# LineAmp.net
KiCad netlist of a schematic drawn in EAGLE
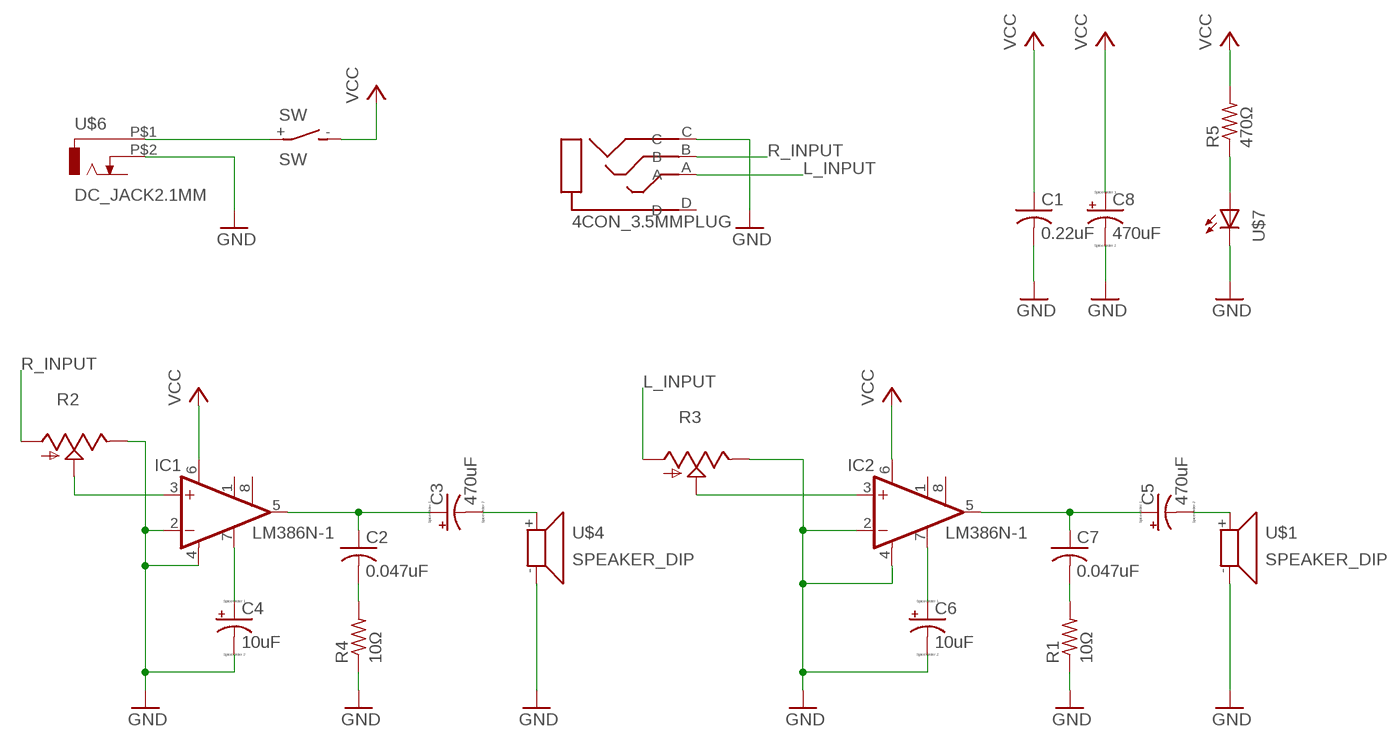
[diagram p0: schematic, sheet 1]

(export (version "E")
  (design (tool "Eeschema 10.0.6"))
  (components
    (comp (ref "C1")
      (value "0.22uF")
      (footprint "eagle-import:C075-042X103")
      (libsource (lib "eagle-import") (part "C-US075-042X103"))
    )
    (comp (ref "C2")
      (value "0.047uF")
      (footprint "eagle-import:C050-024X044")
      (libsource (lib "eagle-import") (part "C-US050-024X044"))
    )
    (comp (ref "C3")
      (value "470uF")
      (footprint "eagle-import:E7,5-16")
      (libsource (lib "eagle-import") (part "CPOL-USE7.5-16"))
    )
    (comp (ref "C4")
      (value "10uF")
      (footprint "eagle-import:E2-5")
      (libsource (lib "eagle-import") (part "CPOL-USE2-5"))
    )
    (comp (ref "C5")
      (value "470uF")
      (footprint "eagle-import:E7,5-16")
      (libsource (lib "eagle-import") (part "CPOL-USE7.5-16"))
    )
    (comp (ref "C6")
      (value "10uF")
      (footprint "eagle-import:E2-5")
      (libsource (lib "eagle-import") (part "CPOL-USE2-5"))
    )
    (comp (ref "C7")
      (value "0.047uF")
      (footprint "eagle-import:C050-024X044")
      (libsource (lib "eagle-import") (part "C-US050-024X044"))
    )
    (comp (ref "C8")
      (value "470uF")
      (footprint "eagle-import:E7,5-16")
      (libsource (lib "eagle-import") (part "CPOL-USE7.5-16"))
    )
    (comp (ref "IC1")
      (value "LM386N-1")
      (footprint "eagle-import:DIL08")
      (libsource (lib "eagle-import") (part "LM386?-N1"))
    )
    (comp (ref "IC2")
      (value "LM386N-1")
      (footprint "eagle-import:DIL08")
      (libsource (lib "eagle-import") (part "LM386?-N1"))
    )
    (comp (ref "R1")
      (value "10Ω")
      (footprint "eagle-import:M1206")
      (libsource (lib "eagle-import") (part "R-US_M1206"))
    )
    (comp (ref "R2")
      (value "TRIM_US-ALPS-PANEL")
      (footprint "eagle-import:ALPS-POT-PANEL")
      (libsource (lib "eagle-import") (part "TRIM_US-ALPS-PANEL"))
    )
    (comp (ref "R3")
      (value "TRIM_US-ALPS-PANEL")
      (footprint "eagle-import:ALPS-POT-PANEL")
      (libsource (lib "eagle-import") (part "TRIM_US-ALPS-PANEL"))
    )
    (comp (ref "R4")
      (value "10Ω")
      (footprint "eagle-import:M1206")
      (libsource (lib "eagle-import") (part "R-US_M1206"))
    )
    (comp (ref "R5")
      (value "470Ω")
      (footprint "eagle-import:M1206")
      (libsource (lib "eagle-import") (part "R-US_M1206"))
    )
    (comp (ref "SW")
      (value "SW")
      (footprint "eagle-import:2PIN_DIP")
      (libsource (lib "eagle-import") (part "SW"))
    )
    (comp (ref "U$1")
      (value "SPEAKER_DIP")
      (footprint "eagle-import:2PIN_DIP")
      (libsource (lib "eagle-import") (part "SPEAKER_DIP"))
    )
    (comp (ref "U$4")
      (value "SPEAKER_DIP")
      (footprint "eagle-import:2PIN_DIP")
      (libsource (lib "eagle-import") (part "SPEAKER_DIP"))
    )
    (comp (ref "U$5")
      (value "4CON_3.5MMPLUG")
      (footprint "eagle-import:4PIN_DIP")
      (libsource (lib "eagle-import") (part "4CON_3.5MMPLUG"))
    )
    (comp (ref "U$6")
      (value "DC_JACK2.1MM")
      (footprint "eagle-import:DC_JACK2.1MM")
      (libsource (lib "eagle-import") (part "DC_JACK2.1MM"))
    )
    (comp (ref "U$7")
      (value "LED5MM")
      (footprint "eagle-import:5MM")
      (libsource (lib "eagle-import") (part "LED5MM"))
    )
  )
  (nets
    (net (code "1") (name "/L_INPUT") (class "Default")
      (node (ref "R3") (pin "P$3") (pinfunction "A_P$3") (pintype "passive"))
      (node (ref "U$5") (pin "A") (pinfunction "A_A") (pintype "bidirectional"))
    )
    (net (code "2") (name "/R_INPUT") (class "Default")
      (node (ref "R2") (pin "P$3") (pinfunction "A_P$3") (pintype "passive"))
      (node (ref "U$5") (pin "B") (pinfunction "B_B") (pintype "bidirectional"))
    )
    (net (code "3") (name "GND") (class "Default")
      (node (ref "C1") (pin "2") (pinfunction "2_2") (pintype "passive"))
      (node (ref "C4") (pin "-") (pinfunction "-_-") (pintype "passive"))
      (node (ref "C6") (pin "-") (pinfunction "-_-") (pintype "passive"))
      (node (ref "C8") (pin "-") (pinfunction "-_-") (pintype "passive"))
      (node (ref "IC1") (pin "2") (pinfunction "-IN_2") (pintype "input"))
      (node (ref "IC1") (pin "4") (pinfunction "GND_4") (pintype "power_in"))
      (node (ref "IC2") (pin "2") (pinfunction "-IN_2") (pintype "input"))
      (node (ref "IC2") (pin "4") (pinfunction "GND_4") (pintype "power_in"))
      (node (ref "R1") (pin "1") (pinfunction "1_1") (pintype "passive"))
      (node (ref "R2") (pin "P$1") (pinfunction "E_P$1") (pintype "passive"))
      (node (ref "R3") (pin "P$1") (pinfunction "E_P$1") (pintype "passive"))
      (node (ref "R4") (pin "1") (pinfunction "1_1") (pintype "passive"))
      (node (ref "U$1") (pin "-") (pinfunction "-_-") (pintype "passive"))
      (node (ref "U$4") (pin "-") (pinfunction "-_-") (pintype "passive"))
      (node (ref "U$5") (pin "C") (pinfunction "C_C") (pintype "bidirectional"))
      (node (ref "U$6") (pin "P$2") (pinfunction "2_P$2") (pintype "passive"))
      (node (ref "U$7") (pin "OUT") (pinfunction "C_OUT") (pintype "passive"))
    )
    (net (code "4") (name "Net-(C2-Pad2)") (class "Default")
      (node (ref "C2") (pin "2") (pinfunction "2_2") (pintype "passive"))
      (node (ref "R4") (pin "2") (pinfunction "2_2") (pintype "passive"))
    )
    (net (code "5") (name "Net-(C3-Pad-)") (class "Default")
      (node (ref "C3") (pin "-") (pinfunction "-_-") (pintype "passive"))
      (node (ref "U$4") (pin "+") (pinfunction "+_+") (pintype "passive"))
    )
    (net (code "6") (name "Net-(C5-Pad-)") (class "Default")
      (node (ref "C5") (pin "-") (pinfunction "-_-") (pintype "passive"))
      (node (ref "U$1") (pin "+") (pinfunction "+_+") (pintype "passive"))
    )
    (net (code "7") (name "Net-(C7-Pad2)") (class "Default")
      (node (ref "C7") (pin "2") (pinfunction "2_2") (pintype "passive"))
      (node (ref "R1") (pin "2") (pinfunction "2_2") (pintype "passive"))
    )
    (net (code "8") (name "Net-(IC1-+IN)") (class "Default")
      (node (ref "IC1") (pin "3") (pinfunction "+IN_3") (pintype "input"))
      (node (ref "R2") (pin "P$2") (pinfunction "S_P$2") (pintype "passive"))
    )
    (net (code "9") (name "Net-(IC1-BYPASS)") (class "Default")
      (node (ref "C4") (pin "+") (pinfunction "+_+") (pintype "passive"))
      (node (ref "IC1") (pin "7") (pinfunction "BYPASS_7") (pintype "passive"))
    )
    (net (code "10") (name "Net-(IC1-OUT)") (class "Default")
      (node (ref "C2") (pin "1") (pinfunction "1_1") (pintype "passive"))
      (node (ref "C3") (pin "+") (pinfunction "+_+") (pintype "passive"))
      (node (ref "IC1") (pin "5") (pinfunction "OUT_5") (pintype "output"))
    )
    (net (code "11") (name "Net-(IC2-+IN)") (class "Default")
      (node (ref "IC2") (pin "3") (pinfunction "+IN_3") (pintype "input"))
      (node (ref "R3") (pin "P$2") (pinfunction "S_P$2") (pintype "passive"))
    )
    (net (code "12") (name "Net-(IC2-BYPASS)") (class "Default")
      (node (ref "C6") (pin "+") (pinfunction "+_+") (pintype "passive"))
      (node (ref "IC2") (pin "7") (pinfunction "BYPASS_7") (pintype "passive"))
    )
    (net (code "13") (name "Net-(IC2-OUT)") (class "Default")
      (node (ref "C5") (pin "+") (pinfunction "+_+") (pintype "passive"))
      (node (ref "C7") (pin "1") (pinfunction "1_1") (pintype "passive"))
      (node (ref "IC2") (pin "5") (pinfunction "OUT_5") (pintype "output"))
    )
    (net (code "14") (name "Net-(SW-P)") (class "Default")
      (node (ref "SW") (pin "+") (pinfunction "P_+") (pintype "passive"))
      (node (ref "U$6") (pin "P$1") (pinfunction "1_P$1") (pintype "passive"))
    )
    (net (code "15") (name "Net-(U$7-A)") (class "Default")
      (node (ref "R5") (pin "1") (pinfunction "1_1") (pintype "passive"))
      (node (ref "U$7") (pin "IN") (pinfunction "A_IN") (pintype "passive"))
    )
    (net (code "16") (name "VCC") (class "Default")
      (node (ref "C1") (pin "1") (pinfunction "1_1") (pintype "passive"))
      (node (ref "C8") (pin "+") (pinfunction "+_+") (pintype "passive"))
      (node (ref "IC1") (pin "6") (pinfunction "VS_6") (pintype "power_in"))
      (node (ref "IC2") (pin "6") (pinfunction "VS_6") (pintype "power_in"))
      (node (ref "R5") (pin "2") (pinfunction "2_2") (pintype "passive"))
      (node (ref "SW") (pin "-") (pinfunction "S_-") (pintype "passive"))
    )
    (net (code "17") (name "unconnected-(IC1-GAIN-Pad1)") (class "Default")
      (node (ref "IC1") (pin "1") (pinfunction "GAIN_1") (pintype "passive"))
    )
    (net (code "18") (name "unconnected-(IC1-GAIN-Pad8)") (class "Default")
      (node (ref "IC1") (pin "8") (pinfunction "GAIN_8") (pintype "passive"))
    )
    (net (code "19") (name "unconnected-(IC2-GAIN-Pad1)") (class "Default")
      (node (ref "IC2") (pin "1") (pinfunction "GAIN_1") (pintype "passive"))
    )
    (net (code "20") (name "unconnected-(IC2-GAIN-Pad8)") (class "Default")
      (node (ref "IC2") (pin "8") (pinfunction "GAIN_8") (pintype "passive"))
    )
    (net (code "21") (name "unconnected-(U$5-PadD)") (class "Default")
      (node (ref "U$5") (pin "D") (pinfunction "D_D") (pintype "bidirectional"))
    )
  )
)
